# Serial_LCD_Backpack_v28.net
KiCad netlist of a schematic drawn in EAGLE
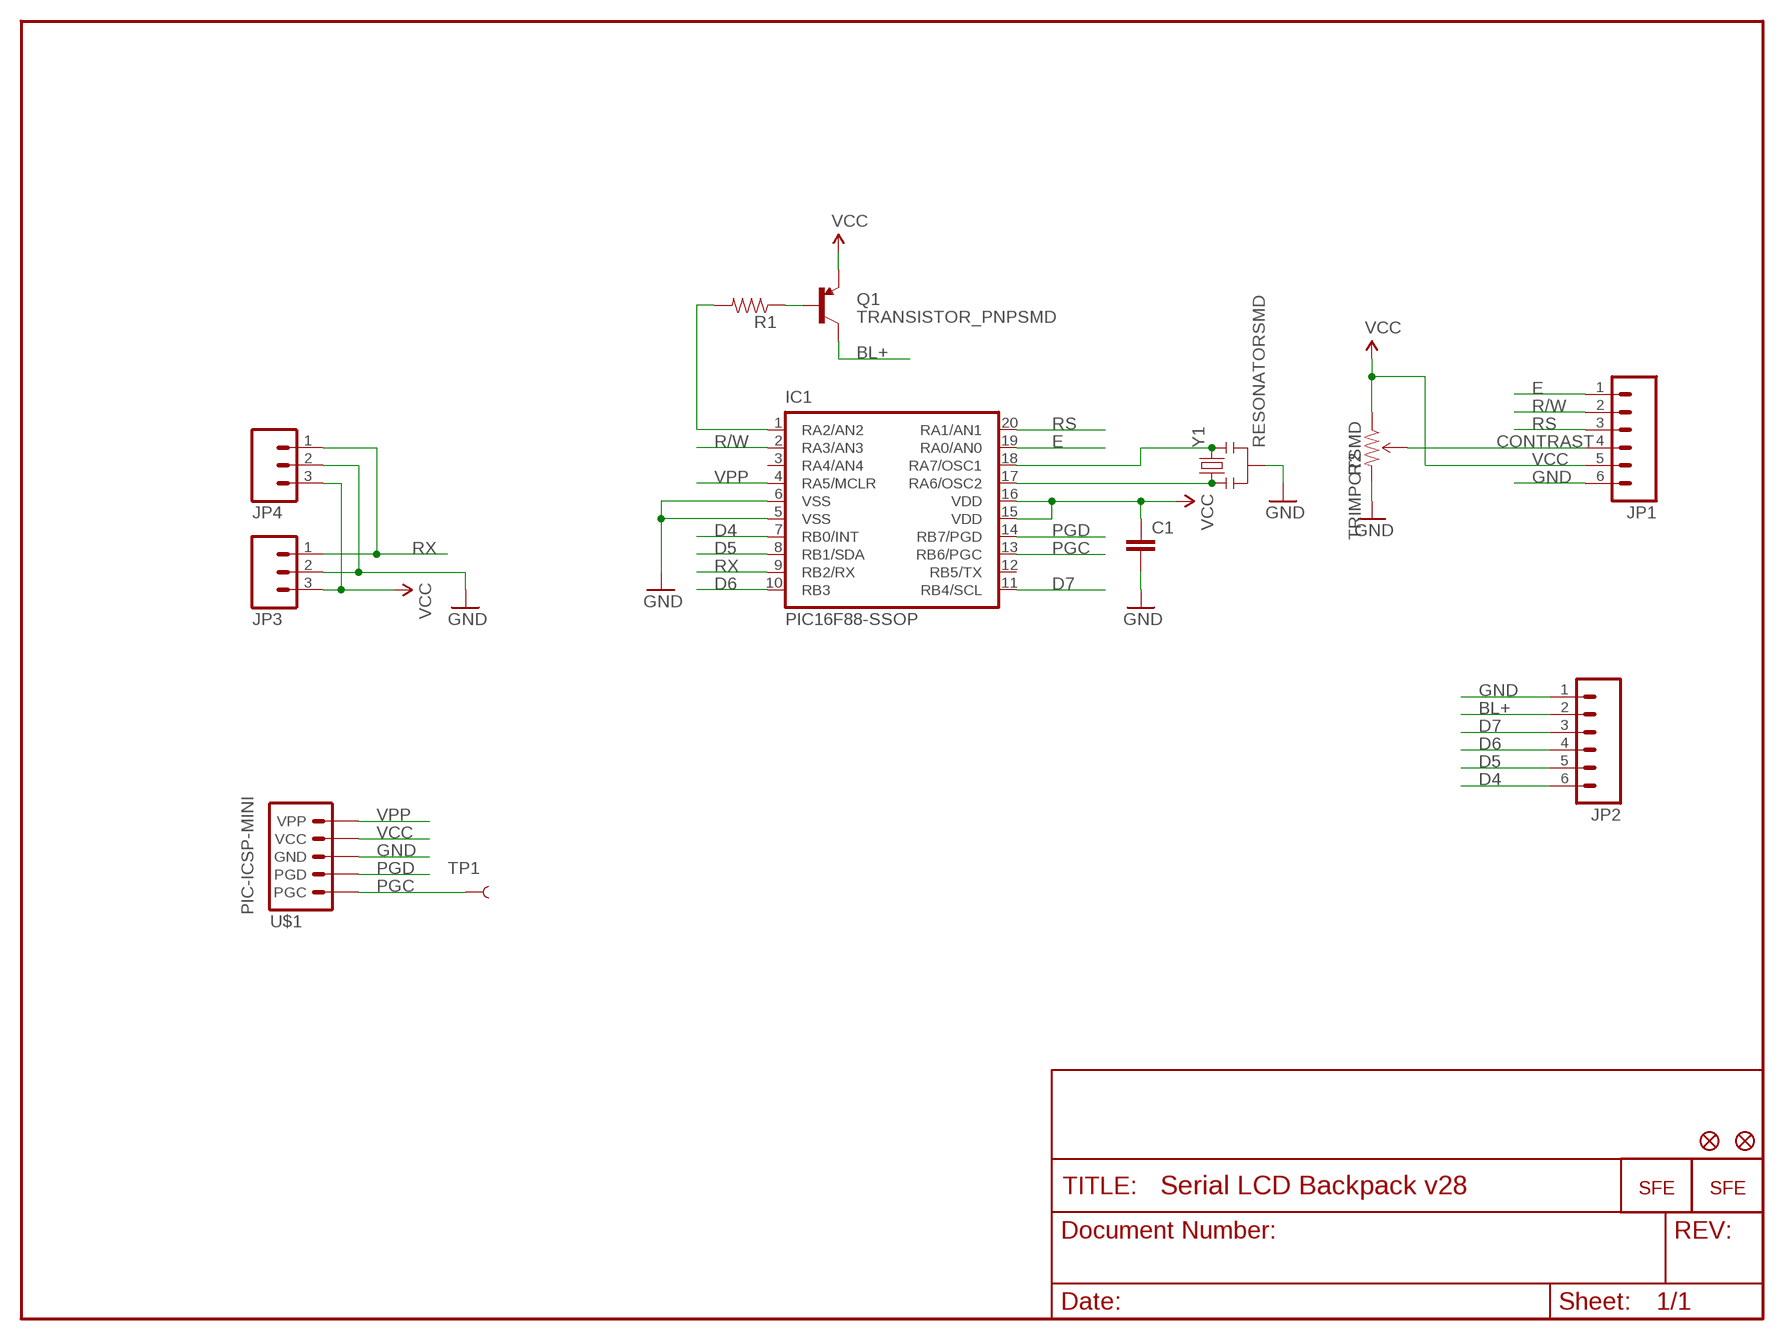
[diagram p0: schematic, sheet 1]

(export (version "E")
  (design (tool "Eeschema 10.0.6"))
  (components
    (comp (ref "C1")
      (value "CAP0402-CAP")
      (footprint "eagle-import:0402-CAP")
      (libsource (lib "eagle-import") (part "CAP0402-CAP"))
    )
    (comp (ref "IC1")
      (value "PIC16F88-SSOP")
      (footprint "eagle-import:SSOP20")
      (libsource (lib "eagle-import") (part "PIC16F88-SSOP"))
    )
    (comp (ref "JP1")
      (value "M06LOCK")
      (footprint "eagle-import:1X06_LOCK")
      (libsource (lib "eagle-import") (part "M06LOCK"))
    )
    (comp (ref "JP2")
      (value "M06LOCK")
      (footprint "eagle-import:1X06_LOCK")
      (libsource (lib "eagle-import") (part "M06LOCK"))
    )
    (comp (ref "JP3")
      (value "M03PTH")
      (footprint "eagle-import:1X03")
      (libsource (lib "eagle-import") (part "M03PTH"))
    )
    (comp (ref "JP4")
      (value "M03SCREW_LOCK")
      (footprint "eagle-import:SCREWTERMINAL-3.5MM-3_LOCK.007S")
      (libsource (lib "eagle-import") (part "M03SCREW_LOCK"))
    )
    (comp (ref "Q1")
      (value "TRANSISTOR_PNPSMD")
      (footprint "eagle-import:SOT23-3")
      (libsource (lib "eagle-import") (part "TRANSISTOR_PNPSMD"))
    )
    (comp (ref "R1")
      (value "RESISTOR0402-RES")
      (footprint "eagle-import:0402-RES")
      (libsource (lib "eagle-import") (part "RESISTOR0402-RES"))
    )
    (comp (ref "R2")
      (value "TRIMPOTSMD")
      (footprint "eagle-import:TRIMPOT-3MM")
      (libsource (lib "eagle-import") (part "TRIMPOTSMD"))
    )
    (comp (ref "TP1")
      (value "TEST-POINT3X5")
      (footprint "eagle-import:PAD.03X.05")
      (libsource (lib "eagle-import") (part "TEST-POINT3X5"))
    )
    (comp (ref "U$1")
      (value "PIC-ICSP-MINI")
      (footprint "eagle-import:PIC-ICSP-MINI")
      (libsource (lib "eagle-import") (part "PIC-ICSP-MINI"))
    )
    (comp (ref "U$2")
      (value "LOGO-FLAME-LARGE")
      (footprint "eagle-import:LOGO-FLAME-LARGE")
      (libsource (lib "eagle-import") (part "LOGO-FLAME-LARGE"))
    )
    (comp (ref "U$3")
      (value "FIDUCIAL1X2")
      (footprint "eagle-import:FIDUCIAL-1X2")
      (libsource (lib "eagle-import") (part "FIDUCIAL1X2"))
    )
    (comp (ref "U$4")
      (value "FIDUCIAL1X2")
      (footprint "eagle-import:FIDUCIAL-1X2")
      (libsource (lib "eagle-import") (part "FIDUCIAL1X2"))
    )
    (comp (ref "U$5")
      (value "LOGO-SFENEW")
      (footprint "eagle-import:SFE-NEW-WEBLOGO")
      (libsource (lib "eagle-import") (part "LOGO-SFENEW"))
    )
    (comp (ref "Y1")
      (value "RESONATORSMD")
      (footprint "eagle-import:RESONATOR-SMD")
      (libsource (lib "eagle-import") (part "RESONATORSMD"))
    )
  )
  (nets
    (net (code "1") (name "/BL+") (class "Default")
      (node (ref "JP2") (pin "2") (pinfunction "2_2") (pintype "passive"))
      (node (ref "Q1") (pin "3") (pinfunction "C_3") (pintype "passive"))
    )
    (net (code "2") (name "/CONTRAST") (class "Default")
      (node (ref "JP1") (pin "4") (pinfunction "4_4") (pintype "passive"))
      (node (ref "R2") (pin "2") (pinfunction "WIPER_2") (pintype "passive"))
    )
    (net (code "3") (name "/D4") (class "Default")
      (node (ref "IC1") (pin "7") (pinfunction "RB0/INT_7") (pintype "bidirectional"))
      (node (ref "JP2") (pin "6") (pinfunction "6_6") (pintype "passive"))
    )
    (net (code "4") (name "/D5") (class "Default")
      (node (ref "IC1") (pin "8") (pinfunction "RB1/SDA_8") (pintype "bidirectional"))
      (node (ref "JP2") (pin "5") (pinfunction "5_5") (pintype "passive"))
    )
    (net (code "5") (name "/D6") (class "Default")
      (node (ref "IC1") (pin "10") (pinfunction "RB3_10") (pintype "bidirectional"))
      (node (ref "JP2") (pin "4") (pinfunction "4_4") (pintype "passive"))
    )
    (net (code "6") (name "/D7") (class "Default")
      (node (ref "IC1") (pin "11") (pinfunction "RB4/SCL_11") (pintype "bidirectional"))
      (node (ref "JP2") (pin "3") (pinfunction "3_3") (pintype "passive"))
    )
    (net (code "7") (name "/E") (class "Default")
      (node (ref "IC1") (pin "19") (pinfunction "RA0/AN0_19") (pintype "bidirectional"))
      (node (ref "JP1") (pin "1") (pinfunction "1_1") (pintype "passive"))
    )
    (net (code "8") (name "/PGC") (class "Default")
      (node (ref "IC1") (pin "13") (pinfunction "RB6/PGC_13") (pintype "bidirectional"))
      (node (ref "TP1") (pin "P$1") (pinfunction "1_P$1") (pintype "bidirectional"))
      (node (ref "U$1") (pin "5") (pinfunction "PGC_5") (pintype "passive"))
    )
    (net (code "9") (name "/PGD") (class "Default")
      (node (ref "IC1") (pin "14") (pinfunction "RB7/PGD_14") (pintype "bidirectional"))
      (node (ref "U$1") (pin "4") (pinfunction "PGD_4") (pintype "passive"))
    )
    (net (code "10") (name "/RS") (class "Default")
      (node (ref "IC1") (pin "20") (pinfunction "RA1/AN1_20") (pintype "bidirectional"))
      (node (ref "JP1") (pin "3") (pinfunction "3_3") (pintype "passive"))
    )
    (net (code "11") (name "/RX") (class "Default")
      (node (ref "IC1") (pin "9") (pinfunction "RB2/RX_9") (pintype "bidirectional"))
      (node (ref "JP3") (pin "1") (pinfunction "1_1") (pintype "passive"))
      (node (ref "JP4") (pin "1") (pinfunction "1_1") (pintype "passive"))
    )
    (net (code "12") (name "/R{slash}W") (class "Default")
      (node (ref "IC1") (pin "2") (pinfunction "RA3/AN3_2") (pintype "bidirectional"))
      (node (ref "JP1") (pin "2") (pinfunction "2_2") (pintype "passive"))
    )
    (net (code "13") (name "/VPP") (class "Default")
      (node (ref "IC1") (pin "4") (pinfunction "RA5/MCLR_4") (pintype "input"))
      (node (ref "U$1") (pin "1") (pinfunction "VPP_1") (pintype "passive"))
    )
    (net (code "14") (name "GND") (class "Default")
      (node (ref "C1") (pin "2") (pinfunction "2_2") (pintype "passive"))
      (node (ref "IC1") (pin "5") (pinfunction "VSS_5") (pintype "power_in"))
      (node (ref "IC1") (pin "6") (pinfunction "VSS_6") (pintype "power_in"))
      (node (ref "JP1") (pin "6") (pinfunction "6_6") (pintype "passive"))
      (node (ref "JP2") (pin "1") (pinfunction "1_1") (pintype "passive"))
      (node (ref "JP3") (pin "2") (pinfunction "2_2") (pintype "passive"))
      (node (ref "JP4") (pin "2") (pinfunction "2_2") (pintype "passive"))
      (node (ref "R2") (pin "3") (pinfunction "CW_3") (pintype "passive"))
      (node (ref "U$1") (pin "3") (pinfunction "GND_3") (pintype "passive"))
      (node (ref "Y1") (pin "2") (pinfunction "2_2") (pintype "passive"))
    )
    (net (code "15") (name "Net-(IC1-RA2{slash}AN2)") (class "Default")
      (node (ref "IC1") (pin "1") (pinfunction "RA2/AN2_1") (pintype "bidirectional"))
      (node (ref "R1") (pin "2") (pinfunction "2_2") (pintype "passive"))
    )
    (net (code "16") (name "Net-(IC1-RA6{slash}OSC2)") (class "Default")
      (node (ref "IC1") (pin "17") (pinfunction "RA6/OSC2_17") (pintype "bidirectional"))
      (node (ref "Y1") (pin "1") (pinfunction "1_1") (pintype "passive"))
    )
    (net (code "17") (name "Net-(IC1-RA7{slash}OSC1)") (class "Default")
      (node (ref "IC1") (pin "18") (pinfunction "RA7/OSC1_18") (pintype "bidirectional"))
      (node (ref "Y1") (pin "3") (pinfunction "3_3") (pintype "passive"))
    )
    (net (code "18") (name "Net-(Q1-B)") (class "Default")
      (node (ref "Q1") (pin "1") (pinfunction "B_1") (pintype "passive"))
      (node (ref "R1") (pin "1") (pinfunction "1_1") (pintype "passive"))
    )
    (net (code "19") (name "VCC") (class "Default")
      (node (ref "C1") (pin "1") (pinfunction "1_1") (pintype "passive"))
      (node (ref "IC1") (pin "15") (pinfunction "VDD_15") (pintype "power_in"))
      (node (ref "IC1") (pin "16") (pinfunction "VDD_16") (pintype "power_in"))
      (node (ref "JP1") (pin "5") (pinfunction "5_5") (pintype "passive"))
      (node (ref "JP3") (pin "3") (pinfunction "3_3") (pintype "passive"))
      (node (ref "JP4") (pin "3") (pinfunction "3_3") (pintype "passive"))
      (node (ref "Q1") (pin "2") (pinfunction "E_2") (pintype "passive"))
      (node (ref "R2") (pin "1") (pinfunction "CCW_1") (pintype "passive"))
      (node (ref "U$1") (pin "2") (pinfunction "VCC_2") (pintype "passive"))
    )
    (net (code "20") (name "unconnected-(IC1-RA4{slash}AN4-Pad3)") (class "Default")
      (node (ref "IC1") (pin "3") (pinfunction "RA4/AN4_3") (pintype "bidirectional"))
    )
    (net (code "21") (name "unconnected-(IC1-RB5{slash}TX-Pad12)") (class "Default")
      (node (ref "IC1") (pin "12") (pinfunction "RB5/TX_12") (pintype "bidirectional"))
    )
  )
)
